# Main.net
KiCad netlist of a schematic drawn in EAGLE
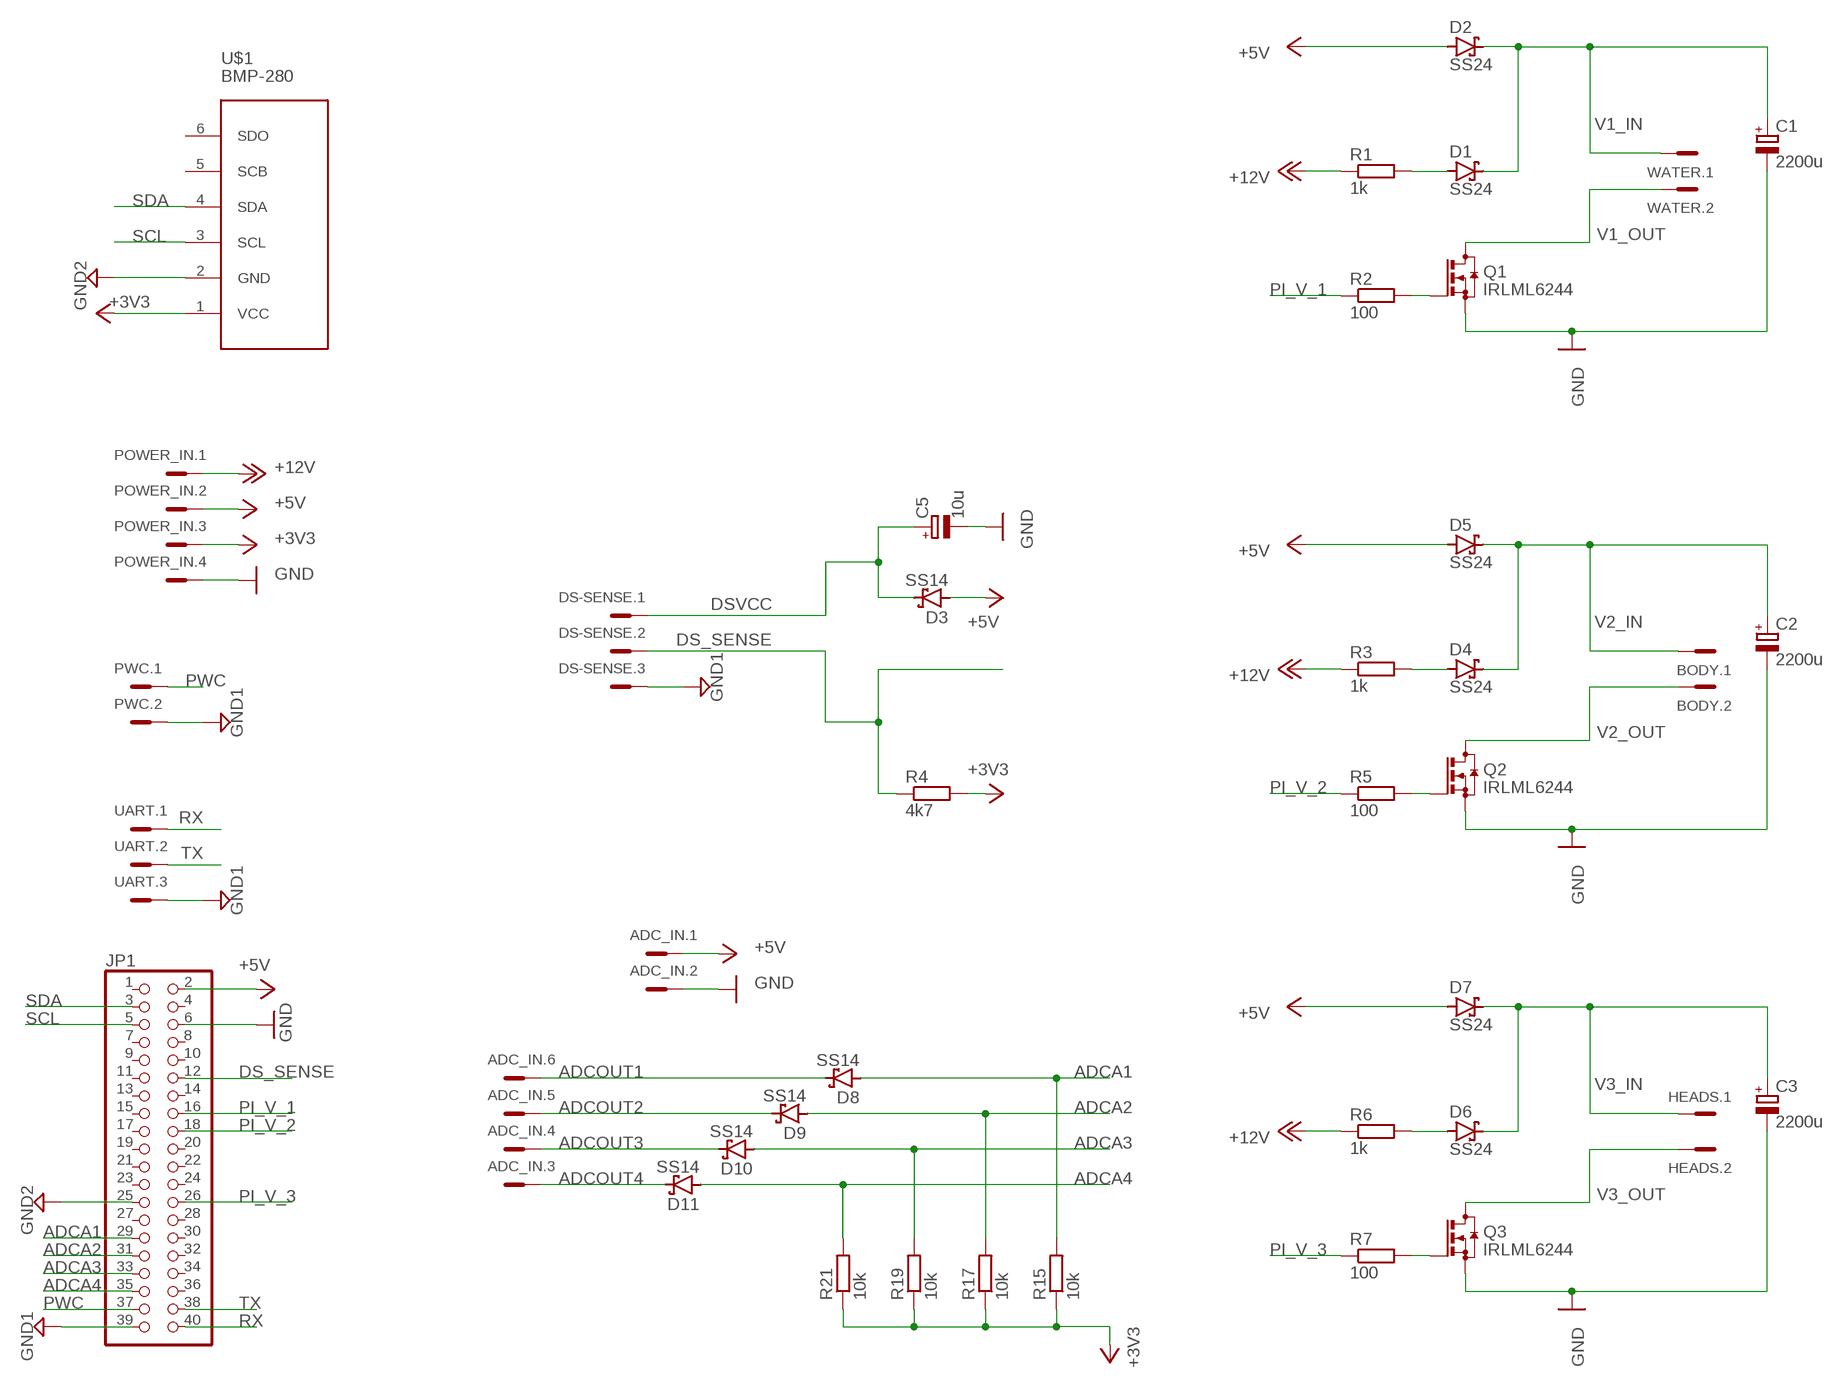
[diagram p0: schematic, sheet 1]

(export (version "E")
  (design (tool "Eeschema 10.0.6"))
  (components
    (comp (ref "ADC_IN")
      (value "MCV6")
      (footprint "eagle-import:MCV6")
      (libsource (lib "eagle-import") (part "MCV6"))
    )
    (comp (ref "BODY")
      (value "MCV2")
      (footprint "eagle-import:MCV2")
      (libsource (lib "eagle-import") (part "MCV2"))
    )
    (comp (ref "C1")
      (value "2200u")
      (footprint "eagle-import:TT5D10")
      (libsource (lib "eagle-import") (part "CPOL-EUTT5D10"))
    )
    (comp (ref "C2")
      (value "2200u")
      (footprint "eagle-import:TT5D10")
      (libsource (lib "eagle-import") (part "CPOL-EUTT5D10"))
    )
    (comp (ref "C3")
      (value "2200u")
      (footprint "eagle-import:TT5D10")
      (libsource (lib "eagle-import") (part "CPOL-EUTT5D10"))
    )
    (comp (ref "C5")
      (value "10u")
      (footprint "eagle-import:SMC_B")
      (libsource (lib "eagle-import") (part "CPOL-EUSMCB"))
    )
    (comp (ref "D1")
      (value "SS24")
      (footprint "eagle-import:SMB")
      (fields
        (field (name "MANUFACTURER") "JCET")
        (field (name "MPN") "SS54B")
        (field (name "CREATED_BY") "PCBLayout.com")
      )
      (libsource (lib "eagle-import") (part "SS54B"))
    )
    (comp (ref "D2")
      (value "SS24")
      (footprint "eagle-import:SMB")
      (fields
        (field (name "MANUFACTURER") "JCET")
        (field (name "MPN") "SS54B")
        (field (name "CREATED_BY") "PCBLayout.com")
      )
      (libsource (lib "eagle-import") (part "SS54B"))
    )
    (comp (ref "D3")
      (value "SS14")
      (footprint "eagle-import:SMA")
      (fields
        (field (name "DIGIKEY_PART_NUMBER") "SS12FSCT-ND")
        (field (name "MANUFACTURER") "ON Semiconductor")
        (field (name "MPN") "SS12")
        (field (name "CREATED_BY") "PCBLayout.com")
      )
      (libsource (lib "eagle-import") (part "SS12"))
    )
    (comp (ref "D4")
      (value "SS24")
      (footprint "eagle-import:SMB")
      (fields
        (field (name "MANUFACTURER") "JCET")
        (field (name "MPN") "SS54B")
        (field (name "CREATED_BY") "PCBLayout.com")
      )
      (libsource (lib "eagle-import") (part "SS54B"))
    )
    (comp (ref "D5")
      (value "SS24")
      (footprint "eagle-import:SMB")
      (fields
        (field (name "MANUFACTURER") "JCET")
        (field (name "MPN") "SS54B")
        (field (name "CREATED_BY") "PCBLayout.com")
      )
      (libsource (lib "eagle-import") (part "SS54B"))
    )
    (comp (ref "D6")
      (value "SS24")
      (footprint "eagle-import:SMB")
      (fields
        (field (name "MANUFACTURER") "JCET")
        (field (name "MPN") "SS54B")
        (field (name "CREATED_BY") "PCBLayout.com")
      )
      (libsource (lib "eagle-import") (part "SS54B"))
    )
    (comp (ref "D7")
      (value "SS24")
      (footprint "eagle-import:SMB")
      (fields
        (field (name "MANUFACTURER") "JCET")
        (field (name "MPN") "SS54B")
        (field (name "CREATED_BY") "PCBLayout.com")
      )
      (libsource (lib "eagle-import") (part "SS54B"))
    )
    (comp (ref "D8")
      (value "SS14")
      (footprint "eagle-import:SMA")
      (fields
        (field (name "DIGIKEY_PART_NUMBER") "SS12FSCT-ND")
        (field (name "MANUFACTURER") "ON Semiconductor")
        (field (name "MPN") "SS12")
        (field (name "CREATED_BY") "PCBLayout.com")
      )
      (libsource (lib "eagle-import") (part "SS12"))
    )
    (comp (ref "D9")
      (value "SS14")
      (footprint "eagle-import:SMA")
      (fields
        (field (name "DIGIKEY_PART_NUMBER") "SS12FSCT-ND")
        (field (name "MANUFACTURER") "ON Semiconductor")
        (field (name "MPN") "SS12")
        (field (name "CREATED_BY") "PCBLayout.com")
      )
      (libsource (lib "eagle-import") (part "SS12"))
    )
    (comp (ref "D10")
      (value "SS14")
      (footprint "eagle-import:SMA")
      (fields
        (field (name "DIGIKEY_PART_NUMBER") "SS12FSCT-ND")
        (field (name "MANUFACTURER") "ON Semiconductor")
        (field (name "MPN") "SS12")
        (field (name "CREATED_BY") "PCBLayout.com")
      )
      (libsource (lib "eagle-import") (part "SS12"))
    )
    (comp (ref "D11")
      (value "SS14")
      (footprint "eagle-import:SMA")
      (fields
        (field (name "DIGIKEY_PART_NUMBER") "SS12FSCT-ND")
        (field (name "MANUFACTURER") "ON Semiconductor")
        (field (name "MPN") "SS12")
        (field (name "CREATED_BY") "PCBLayout.com")
      )
      (libsource (lib "eagle-import") (part "SS12"))
    )
    (comp (ref "DS-SENSE")
      (value "MCV3")
      (footprint "eagle-import:MCV3")
      (libsource (lib "eagle-import") (part "MCV3"))
    )
    (comp (ref "HEADS")
      (value "MCV2")
      (footprint "eagle-import:MCV2")
      (libsource (lib "eagle-import") (part "MCV2"))
    )
    (comp (ref "JP1")
      (value "PINHD-2X20")
      (footprint "eagle-import:2X20")
      (libsource (lib "eagle-import") (part "PINHD-2X20"))
    )
    (comp (ref "POWER_IN")
      (value "MCV4")
      (footprint "eagle-import:MCV4")
      (libsource (lib "eagle-import") (part "MCV4"))
    )
    (comp (ref "PWC")
      (value "MCV2")
      (footprint "eagle-import:MCV2")
      (libsource (lib "eagle-import") (part "MCV2"))
    )
    (comp (ref "Q1")
      (value "IRLML6244")
      (footprint "eagle-import:SOT23")
      (libsource (lib "eagle-import") (part "BSS123"))
    )
    (comp (ref "Q2")
      (value "IRLML6244")
      (footprint "eagle-import:SOT23")
      (libsource (lib "eagle-import") (part "BSS123"))
    )
    (comp (ref "Q3")
      (value "IRLML6244")
      (footprint "eagle-import:SOT23")
      (libsource (lib "eagle-import") (part "BSS123"))
    )
    (comp (ref "R1")
      (value "1k")
      (footprint "eagle-import:R1206")
      (libsource (lib "eagle-import") (part "resistor_348_R-EU_R1206"))
    )
    (comp (ref "R2")
      (value "100")
      (footprint "eagle-import:R1206")
      (libsource (lib "eagle-import") (part "resistor_348_R-EU_R1206"))
    )
    (comp (ref "R3")
      (value "1k")
      (footprint "eagle-import:R1206")
      (libsource (lib "eagle-import") (part "resistor_348_R-EU_R1206"))
    )
    (comp (ref "R4")
      (value "4k7")
      (footprint "eagle-import:R1206")
      (libsource (lib "eagle-import") (part "R-EU_R1206"))
    )
    (comp (ref "R5")
      (value "100")
      (footprint "eagle-import:R1206")
      (libsource (lib "eagle-import") (part "resistor_348_R-EU_R1206"))
    )
    (comp (ref "R6")
      (value "1k")
      (footprint "eagle-import:R1206")
      (libsource (lib "eagle-import") (part "resistor_348_R-EU_R1206"))
    )
    (comp (ref "R7")
      (value "100")
      (footprint "eagle-import:R1206")
      (libsource (lib "eagle-import") (part "resistor_348_R-EU_R1206"))
    )
    (comp (ref "R15")
      (value "10k")
      (footprint "eagle-import:R1206")
      (libsource (lib "eagle-import") (part "R-EU_R1206"))
    )
    (comp (ref "R17")
      (value "10k")
      (footprint "eagle-import:R1206")
      (libsource (lib "eagle-import") (part "R-EU_R1206"))
    )
    (comp (ref "R19")
      (value "10k")
      (footprint "eagle-import:R1206")
      (libsource (lib "eagle-import") (part "R-EU_R1206"))
    )
    (comp (ref "R21")
      (value "10k")
      (footprint "eagle-import:R1206")
      (libsource (lib "eagle-import") (part "R-EU_R1206"))
    )
    (comp (ref "U$1")
      (value "BMP-280")
      (footprint "eagle-import:BPM-280")
      (libsource (lib "eagle-import") (part "BMP-280"))
    )
    (comp (ref "UART")
      (value "MCV3")
      (footprint "eagle-import:MCV3")
      (libsource (lib "eagle-import") (part "MCV3"))
    )
    (comp (ref "WATER")
      (value "MCV2")
      (footprint "eagle-import:MCV2")
      (libsource (lib "eagle-import") (part "MCV2"))
    )
  )
  (nets
    (net (code "1") (name "+3V3") (class "Default")
      (node (ref "POWER_IN") (pin "3") (pinfunction "SK_3") (pintype "passive"))
      (node (ref "R15") (pin "1") (pinfunction "1_1") (pintype "passive"))
      (node (ref "R17") (pin "1") (pinfunction "1_1") (pintype "passive"))
      (node (ref "R19") (pin "1") (pinfunction "1_1") (pintype "passive"))
      (node (ref "R21") (pin "1") (pinfunction "1_1") (pintype "passive"))
      (node (ref "R4") (pin "2") (pinfunction "2_2") (pintype "passive"))
      (node (ref "U$1") (pin "1") (pinfunction "VCC_1") (pintype "power_in"))
    )
    (net (code "2") (name "+5V") (class "Default")
      (node (ref "ADC_IN") (pin "1") (pinfunction "SK_1") (pintype "passive"))
      (node (ref "D2") (pin "A") (pinfunction "A_A") (pintype "passive"))
      (node (ref "D3") (pin "A") (pinfunction "A_A") (pintype "passive"))
      (node (ref "D5") (pin "A") (pinfunction "A_A") (pintype "passive"))
      (node (ref "D7") (pin "A") (pinfunction "A_A") (pintype "passive"))
      (node (ref "JP1") (pin "2") (pinfunction "2_2") (pintype "passive"))
      (node (ref "POWER_IN") (pin "2") (pinfunction "SK_2") (pintype "passive"))
    )
    (net (code "3") (name "+12V") (class "Default")
      (node (ref "POWER_IN") (pin "1") (pinfunction "SK_1") (pintype "passive"))
      (node (ref "R1") (pin "1") (pinfunction "1_1") (pintype "passive"))
      (node (ref "R3") (pin "1") (pinfunction "1_1") (pintype "passive"))
      (node (ref "R6") (pin "1") (pinfunction "1_1") (pintype "passive"))
    )
    (net (code "4") (name "/ADCA1") (class "Default")
      (node (ref "D8") (pin "A") (pinfunction "A_A") (pintype "passive"))
      (node (ref "JP1") (pin "29") (pinfunction "29_29") (pintype "passive"))
      (node (ref "R15") (pin "2") (pinfunction "2_2") (pintype "passive"))
    )
    (net (code "5") (name "/ADCA2") (class "Default")
      (node (ref "D9") (pin "A") (pinfunction "A_A") (pintype "passive"))
      (node (ref "JP1") (pin "31") (pinfunction "31_31") (pintype "passive"))
      (node (ref "R17") (pin "2") (pinfunction "2_2") (pintype "passive"))
    )
    (net (code "6") (name "/ADCA3") (class "Default")
      (node (ref "D10") (pin "A") (pinfunction "A_A") (pintype "passive"))
      (node (ref "JP1") (pin "33") (pinfunction "33_33") (pintype "passive"))
      (node (ref "R19") (pin "2") (pinfunction "2_2") (pintype "passive"))
    )
    (net (code "7") (name "/ADCA4") (class "Default")
      (node (ref "D11") (pin "A") (pinfunction "A_A") (pintype "passive"))
      (node (ref "JP1") (pin "35") (pinfunction "35_35") (pintype "passive"))
      (node (ref "R21") (pin "2") (pinfunction "2_2") (pintype "passive"))
    )
    (net (code "8") (name "/ADCOUT1") (class "Default")
      (node (ref "ADC_IN") (pin "6") (pinfunction "SK_6") (pintype "passive"))
      (node (ref "D8") (pin "C") (pinfunction "C_C") (pintype "passive"))
    )
    (net (code "9") (name "/ADCOUT2") (class "Default")
      (node (ref "ADC_IN") (pin "5") (pinfunction "SK_5") (pintype "passive"))
      (node (ref "D9") (pin "C") (pinfunction "C_C") (pintype "passive"))
    )
    (net (code "10") (name "/ADCOUT3") (class "Default")
      (node (ref "ADC_IN") (pin "4") (pinfunction "SK_4") (pintype "passive"))
      (node (ref "D10") (pin "C") (pinfunction "C_C") (pintype "passive"))
    )
    (net (code "11") (name "/ADCOUT4") (class "Default")
      (node (ref "ADC_IN") (pin "3") (pinfunction "SK_3") (pintype "passive"))
      (node (ref "D11") (pin "C") (pinfunction "C_C") (pintype "passive"))
    )
    (net (code "12") (name "/DSVCC") (class "Default")
      (node (ref "C5") (pin "+") (pinfunction "+_+") (pintype "passive"))
      (node (ref "D3") (pin "C") (pinfunction "C_C") (pintype "passive"))
      (node (ref "DS-SENSE") (pin "1") (pinfunction "SK_1") (pintype "passive"))
    )
    (net (code "13") (name "/DS_SENSE") (class "Default")
      (node (ref "DS-SENSE") (pin "2") (pinfunction "SK_2") (pintype "passive"))
      (node (ref "JP1") (pin "12") (pinfunction "12_12") (pintype "passive"))
      (node (ref "R4") (pin "1") (pinfunction "1_1") (pintype "passive"))
    )
    (net (code "14") (name "/PI_V_1") (class "Default")
      (node (ref "JP1") (pin "16") (pinfunction "16_16") (pintype "passive"))
      (node (ref "R2") (pin "1") (pinfunction "1_1") (pintype "passive"))
    )
    (net (code "15") (name "/PI_V_2") (class "Default")
      (node (ref "JP1") (pin "18") (pinfunction "18_18") (pintype "passive"))
      (node (ref "R5") (pin "1") (pinfunction "1_1") (pintype "passive"))
    )
    (net (code "16") (name "/PI_V_3") (class "Default")
      (node (ref "JP1") (pin "26") (pinfunction "26_26") (pintype "passive"))
      (node (ref "R7") (pin "1") (pinfunction "1_1") (pintype "passive"))
    )
    (net (code "17") (name "/PWC") (class "Default")
      (node (ref "JP1") (pin "37") (pinfunction "37_37") (pintype "passive"))
      (node (ref "PWC") (pin "1") (pinfunction "SK_1") (pintype "passive"))
    )
    (net (code "18") (name "/RX") (class "Default")
      (node (ref "JP1") (pin "40") (pinfunction "40_40") (pintype "passive"))
      (node (ref "UART") (pin "1") (pinfunction "SK_1") (pintype "passive"))
    )
    (net (code "19") (name "/SCL") (class "Default")
      (node (ref "JP1") (pin "5") (pinfunction "5_5") (pintype "passive"))
      (node (ref "U$1") (pin "3") (pinfunction "SCL_3") (pintype "bidirectional"))
    )
    (net (code "20") (name "/SDA") (class "Default")
      (node (ref "JP1") (pin "3") (pinfunction "3_3") (pintype "passive"))
      (node (ref "U$1") (pin "4") (pinfunction "SDA_4") (pintype "bidirectional"))
    )
    (net (code "21") (name "/TX") (class "Default")
      (node (ref "JP1") (pin "38") (pinfunction "38_38") (pintype "passive"))
      (node (ref "UART") (pin "2") (pinfunction "SK_2") (pintype "passive"))
    )
    (net (code "22") (name "/V1_IN") (class "Default")
      (node (ref "C1") (pin "+") (pinfunction "+_+") (pintype "passive"))
      (node (ref "D1") (pin "C") (pinfunction "C_C") (pintype "passive"))
      (node (ref "D2") (pin "C") (pinfunction "C_C") (pintype "passive"))
      (node (ref "WATER") (pin "1") (pinfunction "SK_1") (pintype "passive"))
    )
    (net (code "23") (name "/V1_OUT") (class "Default")
      (node (ref "Q1") (pin "3") (pinfunction "D_3") (pintype "passive"))
      (node (ref "WATER") (pin "2") (pinfunction "SK_2") (pintype "passive"))
    )
    (net (code "24") (name "/V2_IN") (class "Default")
      (node (ref "BODY") (pin "1") (pinfunction "SK_1") (pintype "passive"))
      (node (ref "C2") (pin "+") (pinfunction "+_+") (pintype "passive"))
      (node (ref "D4") (pin "C") (pinfunction "C_C") (pintype "passive"))
      (node (ref "D5") (pin "C") (pinfunction "C_C") (pintype "passive"))
    )
    (net (code "25") (name "/V2_OUT") (class "Default")
      (node (ref "BODY") (pin "2") (pinfunction "SK_2") (pintype "passive"))
      (node (ref "Q2") (pin "3") (pinfunction "D_3") (pintype "passive"))
    )
    (net (code "26") (name "/V3_IN") (class "Default")
      (node (ref "C3") (pin "+") (pinfunction "+_+") (pintype "passive"))
      (node (ref "D6") (pin "C") (pinfunction "C_C") (pintype "passive"))
      (node (ref "D7") (pin "C") (pinfunction "C_C") (pintype "passive"))
      (node (ref "HEADS") (pin "1") (pinfunction "SK_1") (pintype "passive"))
    )
    (net (code "27") (name "/V3_OUT") (class "Default")
      (node (ref "HEADS") (pin "2") (pinfunction "SK_2") (pintype "passive"))
      (node (ref "Q3") (pin "3") (pinfunction "D_3") (pintype "passive"))
    )
    (net (code "28") (name "GND") (class "Default")
      (node (ref "ADC_IN") (pin "2") (pinfunction "SK_2") (pintype "passive"))
      (node (ref "C1") (pin "-") (pinfunction "-_-") (pintype "passive"))
      (node (ref "C2") (pin "-") (pinfunction "-_-") (pintype "passive"))
      (node (ref "C3") (pin "-") (pinfunction "-_-") (pintype "passive"))
      (node (ref "C5") (pin "-") (pinfunction "-_-") (pintype "passive"))
      (node (ref "JP1") (pin "6") (pinfunction "6_6") (pintype "passive"))
      (node (ref "POWER_IN") (pin "4") (pinfunction "SK_4") (pintype "passive"))
      (node (ref "Q1") (pin "2") (pinfunction "S_2") (pintype "passive"))
      (node (ref "Q2") (pin "2") (pinfunction "S_2") (pintype "passive"))
      (node (ref "Q3") (pin "2") (pinfunction "S_2") (pintype "passive"))
    )
    (net (code "29") (name "GND1") (class "Default")
      (node (ref "DS-SENSE") (pin "3") (pinfunction "SK_3") (pintype "passive"))
      (node (ref "JP1") (pin "39") (pinfunction "39_39") (pintype "passive"))
      (node (ref "PWC") (pin "2") (pinfunction "SK_2") (pintype "passive"))
      (node (ref "UART") (pin "3") (pinfunction "SK_3") (pintype "passive"))
    )
    (net (code "30") (name "GND2") (class "Default")
      (node (ref "JP1") (pin "25") (pinfunction "25_25") (pintype "passive"))
      (node (ref "U$1") (pin "2") (pinfunction "GND_2") (pintype "power_in"))
    )
    (net (code "31") (name "Net-(D1-PadA)") (class "Default")
      (node (ref "D1") (pin "A") (pinfunction "A_A") (pintype "passive"))
      (node (ref "R1") (pin "2") (pinfunction "2_2") (pintype "passive"))
    )
    (net (code "32") (name "Net-(D4-PadA)") (class "Default")
      (node (ref "D4") (pin "A") (pinfunction "A_A") (pintype "passive"))
      (node (ref "R3") (pin "2") (pinfunction "2_2") (pintype "passive"))
    )
    (net (code "33") (name "Net-(D6-PadA)") (class "Default")
      (node (ref "D6") (pin "A") (pinfunction "A_A") (pintype "passive"))
      (node (ref "R6") (pin "2") (pinfunction "2_2") (pintype "passive"))
    )
    (net (code "34") (name "Net-(Q1-G)") (class "Default")
      (node (ref "Q1") (pin "1") (pinfunction "G_1") (pintype "passive"))
      (node (ref "R2") (pin "2") (pinfunction "2_2") (pintype "passive"))
    )
    (net (code "35") (name "Net-(Q2-G)") (class "Default")
      (node (ref "Q2") (pin "1") (pinfunction "G_1") (pintype "passive"))
      (node (ref "R5") (pin "2") (pinfunction "2_2") (pintype "passive"))
    )
    (net (code "36") (name "Net-(Q3-G)") (class "Default")
      (node (ref "Q3") (pin "1") (pinfunction "G_1") (pintype "passive"))
      (node (ref "R7") (pin "2") (pinfunction "2_2") (pintype "passive"))
    )
    (net (code "37") (name "unconnected-(JP1-Pad1)") (class "Default")
      (node (ref "JP1") (pin "1") (pinfunction "1_1") (pintype "passive"))
    )
    (net (code "38") (name "unconnected-(JP1-Pad4)") (class "Default")
      (node (ref "JP1") (pin "4") (pinfunction "4_4") (pintype "passive"))
    )
    (net (code "39") (name "unconnected-(JP1-Pad7)") (class "Default")
      (node (ref "JP1") (pin "7") (pinfunction "7_7") (pintype "passive"))
    )
    (net (code "40") (name "unconnected-(JP1-Pad8)") (class "Default")
      (node (ref "JP1") (pin "8") (pinfunction "8_8") (pintype "passive"))
    )
    (net (code "41") (name "unconnected-(JP1-Pad9)") (class "Default")
      (node (ref "JP1") (pin "9") (pinfunction "9_9") (pintype "passive"))
    )
    (net (code "42") (name "unconnected-(JP1-Pad10)") (class "Default")
      (node (ref "JP1") (pin "10") (pinfunction "10_10") (pintype "passive"))
    )
    (net (code "43") (name "unconnected-(JP1-Pad11)") (class "Default")
      (node (ref "JP1") (pin "11") (pinfunction "11_11") (pintype "passive"))
    )
    (net (code "44") (name "unconnected-(JP1-Pad13)") (class "Default")
      (node (ref "JP1") (pin "13") (pinfunction "13_13") (pintype "passive"))
    )
    (net (code "45") (name "unconnected-(JP1-Pad14)") (class "Default")
      (node (ref "JP1") (pin "14") (pinfunction "14_14") (pintype "passive"))
    )
    (net (code "46") (name "unconnected-(JP1-Pad15)") (class "Default")
      (node (ref "JP1") (pin "15") (pinfunction "15_15") (pintype "passive"))
    )
    (net (code "47") (name "unconnected-(JP1-Pad17)") (class "Default")
      (node (ref "JP1") (pin "17") (pinfunction "17_17") (pintype "passive"))
    )
    (net (code "48") (name "unconnected-(JP1-Pad19)") (class "Default")
      (node (ref "JP1") (pin "19") (pinfunction "19_19") (pintype "passive"))
    )
    (net (code "49") (name "unconnected-(JP1-Pad20)") (class "Default")
      (node (ref "JP1") (pin "20") (pinfunction "20_20") (pintype "passive"))
    )
    (net (code "50") (name "unconnected-(JP1-Pad21)") (class "Default")
      (node (ref "JP1") (pin "21") (pinfunction "21_21") (pintype "passive"))
    )
    (net (code "51") (name "unconnected-(JP1-Pad22)") (class "Default")
      (node (ref "JP1") (pin "22") (pinfunction "22_22") (pintype "passive"))
    )
    (net (code "52") (name "unconnected-(JP1-Pad23)") (class "Default")
      (node (ref "JP1") (pin "23") (pinfunction "23_23") (pintype "passive"))
    )
    (net (code "53") (name "unconnected-(JP1-Pad24)") (class "Default")
      (node (ref "JP1") (pin "24") (pinfunction "24_24") (pintype "passive"))
    )
    (net (code "54") (name "unconnected-(JP1-Pad27)") (class "Default")
      (node (ref "JP1") (pin "27") (pinfunction "27_27") (pintype "passive"))
    )
    (net (code "55") (name "unconnected-(JP1-Pad28)") (class "Default")
      (node (ref "JP1") (pin "28") (pinfunction "28_28") (pintype "passive"))
    )
    (net (code "56") (name "unconnected-(JP1-Pad30)") (class "Default")
      (node (ref "JP1") (pin "30") (pinfunction "30_30") (pintype "passive"))
    )
    (net (code "57") (name "unconnected-(JP1-Pad32)") (class "Default")
      (node (ref "JP1") (pin "32") (pinfunction "32_32") (pintype "passive"))
    )
    (net (code "58") (name "unconnected-(JP1-Pad34)") (class "Default")
      (node (ref "JP1") (pin "34") (pinfunction "34_34") (pintype "passive"))
    )
    (net (code "59") (name "unconnected-(JP1-Pad36)") (class "Default")
      (node (ref "JP1") (pin "36") (pinfunction "36_36") (pintype "passive"))
    )
    (net (code "60") (name "unconnected-(U$1-SCB-Pad5)") (class "Default")
      (node (ref "U$1") (pin "5") (pinfunction "SCB_5") (pintype "bidirectional"))
    )
    (net (code "61") (name "unconnected-(U$1-SDO-Pad6)") (class "Default")
      (node (ref "U$1") (pin "6") (pinfunction "SDO_6") (pintype "bidirectional"))
    )
  )
)
